# Battery_Reader.net
KiCad netlist of a schematic drawn in Altium Designer
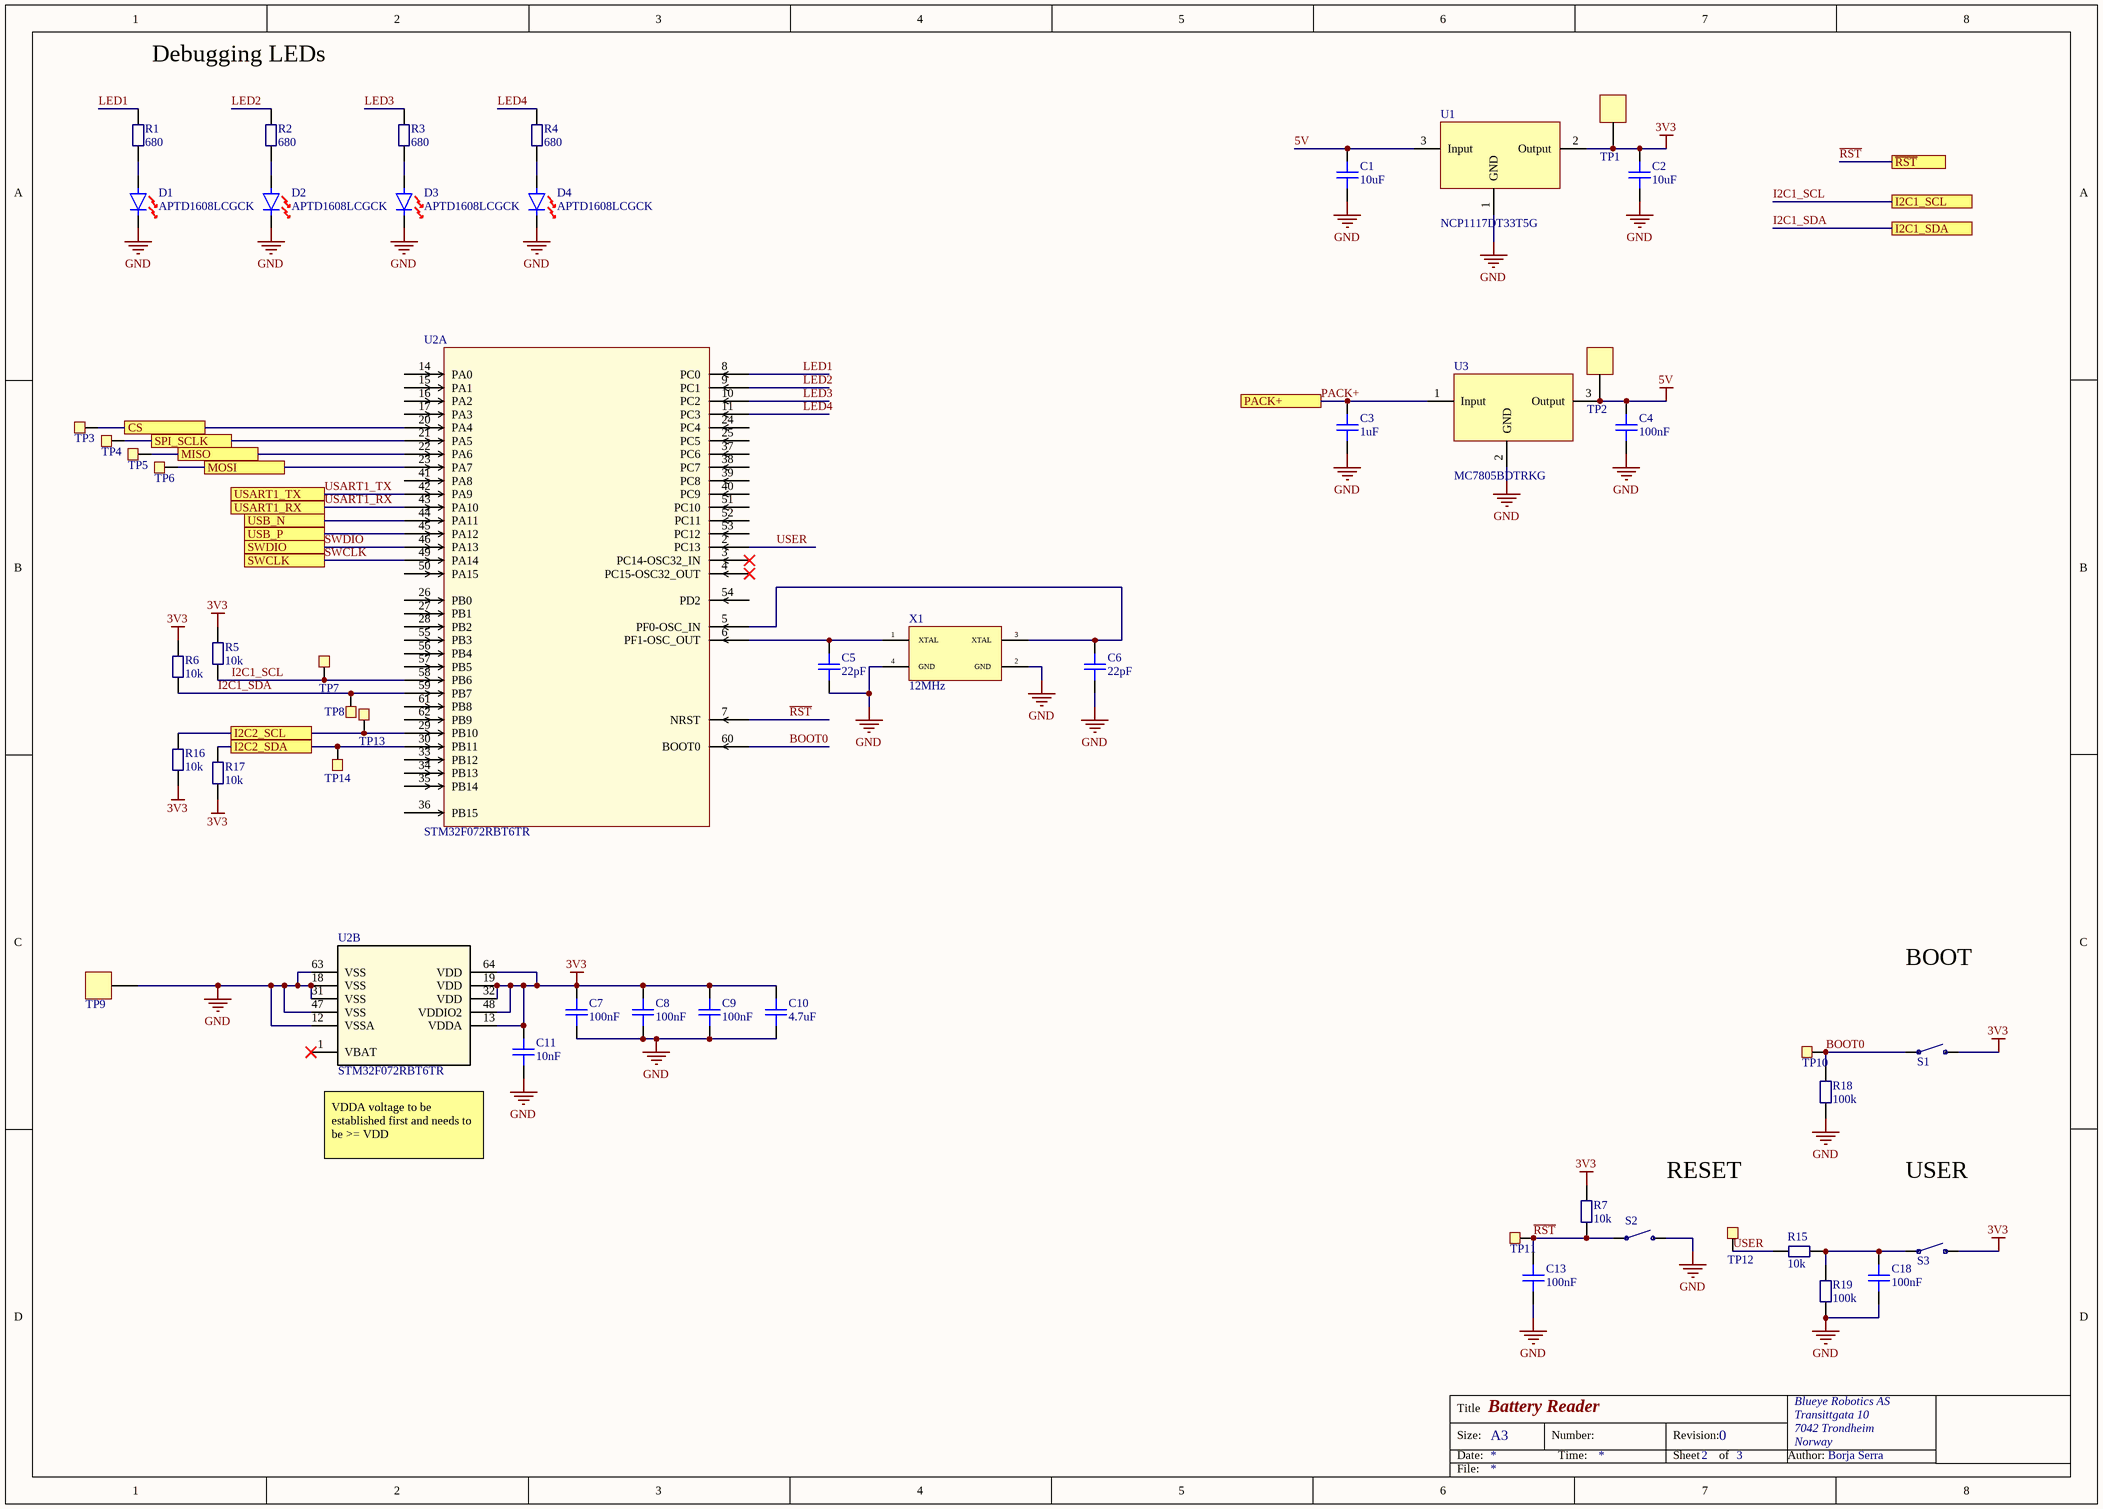
[diagram p0: Battery Reader.SchDoc]

(export (version "E")
  (design (tool "Eeschema 10.0.6"))
  (components
    (comp (ref "C1")
      (value "10uF")
      (footprint "1206 CAPACITOR")
      (description "CAP CER 10UF 35V X7R 1206")
      (fields (field (name "MPN") "GMK316AB7106KL-TR") (field (name "MANUFACTURER") "Taiyo Yuden"))
      (libsource (lib "Battery Reader") (part "CAP CER 10UF 35V X7R 1206"))
    )
    (comp (ref "C2")
      (value "10uF")
      (footprint "1206 CAPACITOR")
      (description "CAP CER 10UF 35V X7R 1206")
      (fields (field (name "MPN") "GMK316AB7106KL-TR") (field (name "MANUFACTURER") "Taiyo Yuden"))
      (libsource (lib "Battery Reader") (part "CAP CER 10UF 35V X7R 1206"))
    )
    (comp (ref "C3")
      (value "1uF")
      (footprint "1206 CAPACITOR")
      (description "Multilayer Ceramic Capacitors MLCC - SMD/SMT 1206 1.0uF 50V X7R 20%")
      (fields (field (name "MANUFACTURER") "TDK") (field (name "MPN") "C3216X7R1H105M160AB"))
      (libsource (lib "Battery Reader") (part "Capacitor 1uF 50V"))
    )
    (comp (ref "C4")
      (value "100nF")
      (footprint "0603 Capacitor")
      (description "CAP CER 0.1UF 50V X7R 0603")
      (fields
        (field (name "MPN") "CL10B104KB8NNNC")
        (field (name "MANUFACTURER") "Samsung Electro-Mechanics")
      )
      (libsource (lib "Battery Reader") (part "CAP CER 0.1UF 50V X7R 0603"))
    )
    (comp (ref "C5")
      (value "22pF")
      (footprint "0603 Capacitor")
      (description "CAP CER 22PF 50V X7R 0603")
      (fields (field (name "MPN") "06035C220JAT2A") (field (name "MANUFACTURER") "AVX Corporation"))
      (libsource (lib "Battery Reader") (part "CAP CER 22PF 50V X7R 0603"))
    )
    (comp (ref "C6")
      (value "22pF")
      (footprint "0603 Capacitor")
      (description "CAP CER 22PF 50V X7R 0603")
      (fields (field (name "MPN") "06035C220JAT2A") (field (name "MANUFACTURER") "AVX Corporation"))
      (libsource (lib "Battery Reader") (part "CAP CER 22PF 50V X7R 0603"))
    )
    (comp (ref "C7")
      (value "100nF")
      (footprint "0603 Capacitor")
      (description "CAP CER 0.1UF 50V X7R 0603")
      (fields
        (field (name "MPN") "CL10B104KB8NNNC")
        (field (name "MANUFACTURER") "Samsung Electro-Mechanics")
      )
      (libsource (lib "Battery Reader") (part "CAP CER 0.1UF 50V X7R 0603"))
    )
    (comp (ref "C8")
      (value "100nF")
      (footprint "0603 Capacitor")
      (description "CAP CER 0.1UF 50V X7R 0603")
      (fields
        (field (name "MPN") "CL10B104KB8NNNC")
        (field (name "MANUFACTURER") "Samsung Electro-Mechanics")
      )
      (libsource (lib "Battery Reader") (part "CAP CER 0.1UF 50V X7R 0603"))
    )
    (comp (ref "C9")
      (value "100nF")
      (footprint "0603 Capacitor")
      (description "CAP CER 0.1UF 50V X7R 0603")
      (fields
        (field (name "MPN") "CL10B104KB8NNNC")
        (field (name "MANUFACTURER") "Samsung Electro-Mechanics")
      )
      (libsource (lib "Battery Reader") (part "CAP CER 0.1UF 50V X7R 0603"))
    )
    (comp (ref "C10")
      (value "4.7uF")
      (footprint "0805 Capacitor")
      (description "Multilayer Ceramic Capacitors MLCC - SMD/SMT 4.7uF 25Volts 10%")
      (fields (field (name "MANUFACTURER") "Murata Electronics") (field (name "MPN") "GRM21BR61E475KA12K"))
      (libsource (lib "Battery Reader") (part "Capacitor 4.7uF 25V"))
    )
    (comp (ref "C11")
      (value "10nF")
      (footprint "0603 Capacitor")
      (description "Multilayer CeramicCapacitors MLCC - SMD/SMT 100volts .01uF 10% X7R AUTO ESD")
      (fields (field (name "MPN") "C0603C103K1RECAUTO") (field (name "MANUFACTURER") "Kemet"))
      (libsource (lib "Battery Reader") (part "Capacitor 10nF"))
    )
    (comp (ref "C13")
      (value "100nF")
      (footprint "0603 Capacitor")
      (description "CAP CER 0.1UF 50V X7R 0603")
      (fields
        (field (name "MPN") "CL10B104KB8NNNC")
        (field (name "MANUFACTURER") "Samsung Electro-Mechanics")
      )
      (libsource (lib "Battery Reader") (part "CAP CER 0.1UF 50V X7R 0603"))
    )
    (comp (ref "C18")
      (value "100nF")
      (footprint "0603 Capacitor")
      (description "CAP CER 0.1UF 50V X7R 0603")
      (fields
        (field (name "MPN") "CL10B104KB8NNNC")
        (field (name "MANUFACTURER") "Samsung Electro-Mechanics")
      )
      (libsource (lib "Battery Reader") (part "CAP CER 0.1UF 50V X7R 0603"))
    )
    (comp (ref "D1")
      (value "APTD1608LCGCK")
      (footprint "0603 LED")
      (description "Standard LEDs - SMD 0603 Dome Lens LED Green- 570nm")
      (fields (field (name "MANUFACTURER") "Kingbright"))
      (libsource (lib "Battery Reader") (part "Standard LEDs - SMD 0603 Dome Lens LED Green- 570nm"))
    )
    (comp (ref "D2")
      (value "APTD1608LCGCK")
      (footprint "0603 LED")
      (description "Standard LEDs - SMD 0603 Dome Lens LED Green- 570nm")
      (fields (field (name "MANUFACTURER") "Kingbright"))
      (libsource (lib "Battery Reader") (part "Standard LEDs - SMD 0603 Dome Lens LED Green- 570nm"))
    )
    (comp (ref "D3")
      (value "APTD1608LCGCK")
      (footprint "0603 LED")
      (description "Standard LEDs - SMD 0603 Dome Lens LED Green- 570nm")
      (fields (field (name "MANUFACTURER") "Kingbright"))
      (libsource (lib "Battery Reader") (part "Standard LEDs - SMD 0603 Dome Lens LED Green- 570nm"))
    )
    (comp (ref "D4")
      (value "APTD1608LCGCK")
      (footprint "0603 LED")
      (description "Standard LEDs - SMD 0603 Dome Lens LED Green- 570nm")
      (fields (field (name "MANUFACTURER") "Kingbright"))
      (libsource (lib "Battery Reader") (part "Standard LEDs - SMD 0603 Dome Lens LED Green- 570nm"))
    )
    (comp (ref "R1")
      (value "680")
      (footprint "0603 Resistor")
      (description "Thick Film Resistors - SMD 0603 680ohms 5% AEC-Q200")
      (fields (field (name "MPN") "ERJ-3GEYJ681V") (field (name "MANUFACTURER") "Panasonic"))
      (libsource (lib "Battery Reader") (part "resistor 680 ohm"))
    )
    (comp (ref "R2")
      (value "680")
      (footprint "0603 Resistor")
      (description "Thick Film Resistors - SMD 0603 680ohms 5% AEC-Q200")
      (fields (field (name "MPN") "ERJ-3GEYJ681V") (field (name "MANUFACTURER") "Panasonic"))
      (libsource (lib "Battery Reader") (part "resistor 680 ohm"))
    )
    (comp (ref "R3")
      (value "680")
      (footprint "0603 Resistor")
      (description "Thick Film Resistors - SMD 0603 680ohms 5% AEC-Q200")
      (fields (field (name "MPN") "ERJ-3GEYJ681V") (field (name "MANUFACTURER") "Panasonic"))
      (libsource (lib "Battery Reader") (part "resistor 680 ohm"))
    )
    (comp (ref "R4")
      (value "680")
      (footprint "0603 Resistor")
      (description "Thick Film Resistors - SMD 0603 680ohms 5% AEC-Q200")
      (fields (field (name "MPN") "ERJ-3GEYJ681V") (field (name "MANUFACTURER") "Panasonic"))
      (libsource (lib "Battery Reader") (part "resistor 680 ohm"))
    )
    (comp (ref "R5")
      (value "10k")
      (footprint "0603 Resistor")
      (description "RES SMD 10K OHM 5% 1/10W 0603")
      (fields (field (name "MANUFACTURER") "Yageo") (field (name "MPN") "RC0603JR-0710KL"))
      (libsource (lib "Battery Reader") (part "RES SMD 10K OHM 5% 1/10W 0603"))
    )
    (comp (ref "R6")
      (value "10k")
      (footprint "0603 Resistor")
      (description "RES SMD 10K OHM 5% 1/10W 0603")
      (fields (field (name "MANUFACTURER") "Yageo") (field (name "MPN") "RC0603JR-0710KL"))
      (libsource (lib "Battery Reader") (part "RES SMD 10K OHM 5% 1/10W 0603"))
    )
    (comp (ref "R7")
      (value "10k")
      (footprint "0603 Resistor")
      (description "RES SMD 10K OHM 5% 1/10W 0603")
      (fields (field (name "MANUFACTURER") "Yageo") (field (name "MPN") "RC0603JR-0710KL"))
      (libsource (lib "Battery Reader") (part "RES SMD 10K OHM 5% 1/10W 0603"))
    )
    (comp (ref "R15")
      (value "10k")
      (footprint "0603 Resistor")
      (description "RES SMD 10K OHM 5% 1/10W 0603")
      (fields (field (name "MANUFACTURER") "Yageo") (field (name "MPN") "RC0603JR-0710KL"))
      (libsource (lib "Battery Reader") (part "RES SMD 10K OHM 5% 1/10W 0603"))
    )
    (comp (ref "R16")
      (value "10k")
      (footprint "0603 Resistor")
      (description "RES SMD 10K OHM 5% 1/10W 0603")
      (fields (field (name "MANUFACTURER") "Yageo") (field (name "MPN") "RC0603JR-0710KL"))
      (libsource (lib "Battery Reader") (part "RES SMD 10K OHM 5% 1/10W 0603"))
    )
    (comp (ref "R17")
      (value "10k")
      (footprint "0603 Resistor")
      (description "RES SMD 10K OHM 5% 1/10W 0603")
      (fields (field (name "MANUFACTURER") "Yageo") (field (name "MPN") "RC0603JR-0710KL"))
      (libsource (lib "Battery Reader") (part "RES SMD 10K OHM 5% 1/10W 0603"))
    )
    (comp (ref "R18")
      (value "100k")
      (footprint "0603 Resistor")
      (description "RES SMD 100K OHM 5% 1/10W 0603")
      (fields (field (name "MPN") "RC0603JR-07100KL") (field (name "MANUFACTURER") "Yageo"))
      (libsource (lib "Battery Reader") (part "RES SMD 100K OHM 5% 1/10W 0603"))
    )
    (comp (ref "R19")
      (value "100k")
      (footprint "0603 Resistor")
      (description "RES SMD 100K OHM 5% 1/10W 0603")
      (fields (field (name "MPN") "RC0603JR-07100KL") (field (name "MANUFACTURER") "Yageo"))
      (libsource (lib "Battery Reader") (part "RES SMD 100K OHM 5% 1/10W 0603"))
    )
    (comp (ref "S1")
      (value "Tactile Switches Reset")
      (footprint "Tact Switch - panasonic")
      (description "Tactile Switches 6.0x3.5mm SMD Light Touch Switch")
      (fields (field (name "MANUFACTURER") "Panasonic") (field (name "MPN") "EVQ-PE105K"))
      (libsource (lib "Battery Reader") (part "Tactile Switches Reset"))
    )
    (comp (ref "S2")
      (value "Tactile Switches Reset")
      (footprint "Tact Switch - panasonic")
      (description "Tactile Switches 6.0x3.5mm SMD Light Touch Switch")
      (fields (field (name "MANUFACTURER") "Panasonic") (field (name "MPN") "EVQ-PE105K"))
      (libsource (lib "Battery Reader") (part "Tactile Switches Reset"))
    )
    (comp (ref "S3")
      (value "Tactile Switches Reset")
      (footprint "Tact Switch - panasonic")
      (description "Tactile Switches 6.0x3.5mm SMD Light Touch Switch")
      (fields (field (name "MANUFACTURER") "Panasonic") (field (name "MPN") "EVQ-PE105K"))
      (libsource (lib "Battery Reader") (part "Tactile Switches Reset"))
    )
    (comp (ref "TP1")
      (value "3122-2-00-15-00-00-08-0")
      (footprint "3122-2-00-15-00-00-08-0")
      (description "CONN PC PIN CIRC 0.040DIA GOLD")
      (fields
        (field (name "MANUFACTURER") "Mill-Max")
        (field (name "MANUFACTURER PART NUMBER") "3123-2-00-15-00-00-08-0")
      )
      (libsource (lib "Battery Reader") (part "3122-2-00-15-00-00-08-0"))
    )
    (comp (ref "TP2")
      (value "3122-2-00-15-00-00-08-0")
      (footprint "3122-2-00-15-00-00-08-0")
      (description "CONN PC PIN CIRC 0.040DIA GOLD")
      (fields
        (field (name "MANUFACTURER") "Mill-Max")
        (field (name "MANUFACTURER PART NUMBER") "3123-2-00-15-00-00-08-0")
      )
      (libsource (lib "Battery Reader") (part "3122-2-00-15-00-00-08-0"))
    )
    (comp (ref "TP3")
      (value "Testpoint")
      (footprint "Testpoint")
      (libsource (lib "Battery Reader") (part "Testpoint"))
    )
    (comp (ref "TP4")
      (value "Testpoint")
      (footprint "Testpoint")
      (libsource (lib "Battery Reader") (part "Testpoint"))
    )
    (comp (ref "TP5")
      (value "Testpoint")
      (footprint "Testpoint")
      (libsource (lib "Battery Reader") (part "Testpoint"))
    )
    (comp (ref "TP6")
      (value "Testpoint")
      (footprint "Testpoint")
      (libsource (lib "Battery Reader") (part "Testpoint"))
    )
    (comp (ref "TP7") (value "Testpoint") (footprint "Testpoint") (libsource (lib "") (part "Testpoint_1")))
    (comp (ref "TP8") (value "Testpoint") (footprint "Testpoint") (libsource (lib "") (part "Testpoint_2")))
    (comp (ref "TP9")
      (value "3122-2-00-15-00-00-08-0")
      (footprint "3122-2-00-15-00-00-08-0")
      (description "CONN PC PIN CIRC 0.040DIA GOLD")
      (fields
        (field (name "MANUFACTURER") "Mill-Max")
        (field (name "MANUFACTURER PART NUMBER") "3123-2-00-15-00-00-08-0")
      )
      (libsource (lib "") (part "3122-2-00-15-00-00-08-0_1"))
    )
    (comp (ref "TP10")
      (value "Testpoint")
      (footprint "Testpoint")
      (libsource (lib "Battery Reader") (part "Testpoint"))
    )
    (comp (ref "TP11")
      (value "Testpoint")
      (footprint "Testpoint")
      (libsource (lib "Battery Reader") (part "Testpoint"))
    )
    (comp (ref "TP12") (value "Testpoint") (footprint "Testpoint") (libsource (lib "") (part "Testpoint_1")))
    (comp (ref "TP13") (value "Testpoint") (footprint "Testpoint") (libsource (lib "") (part "Testpoint_1")))
    (comp (ref "TP14") (value "Testpoint") (footprint "Testpoint") (libsource (lib "") (part "Testpoint_2")))
    (comp (ref "U1")
      (value "NCP1117DT33T5G")
      (footprint "DPAK-3")
      (description "IC REG LINEAR 3.3V 1A DPAK-3")
      (fields (field (name "MANUFACTURER") "ON Semiconductor"))
      (libsource (lib "Battery Reader") (part "IC REG LINEAR 3.3V 1A DPAK-3"))
    )
    (comp (ref "U2")
      (value "STM32F072RBT6TR")
      (footprint "LQFP64-10x10mm")
      (fields (field (name "COPYRIGHT") "Copyright (C) 2016 Accelerated Designs. All rights reserved"))
      (libsource (lib "Battery Reader") (part "STM32F072RBT6TR"))
    )
    (comp (ref "U3")
      (value "MC7805BDTRKG")
      (footprint "DPAK-3")
      (description "IC REG LINEAR 5V 1A DPAK-3")
      (fields (field (name "MANUFACTURER") "ON Semiconductor"))
      (libsource (lib "Battery Reader") (part "IC REG LINEAR 5V 1A DPAK-3"))
    )
    (comp (ref "X1")
      (value "12MHz")
      (footprint "FH1200001 12MHz")
      (description "Crystal 12MHz")
      (fields (field (name "MANUFACTURER") "Pericom") (field (name "MPN") "FH1200001"))
      (libsource (lib "Battery Reader") (part "Crystal 12MHz"))
    )
  )
  (nets
    (net (code "1") (name "/BOOT0") (class "Default")
      (node (ref "R18") (pin "2") (pinfunction "2_2") (pintype "passive"))
      (node (ref "S1") (pin "1") (pinfunction "1_1") (pintype "passive"))
      (node (ref "TP10") (pin "1") (pinfunction "1_1") (pintype "passive"))
      (node (ref "U2") (pin "60") (pinfunction "BOOT0_60") (pintype "passive"))
    )
    (net (code "2") (name "/CS") (class "Default")
      (node (ref "TP3") (pin "1") (pinfunction "1_1") (pintype "passive"))
      (node (ref "U2") (pin "20") (pinfunction "PA4_20") (pintype "passive"))
    )
    (net (code "3") (name "/I2C1_SCL") (class "Default")
      (node (ref "R5") (pin "1") (pinfunction "1_1") (pintype "passive"))
      (node (ref "TP7") (pin "1") (pinfunction "1_1") (pintype "passive"))
      (node (ref "U2") (pin "58") (pinfunction "PB6_58") (pintype "passive"))
    )
    (net (code "4") (name "/I2C1_SDA") (class "Default")
      (node (ref "R6") (pin "1") (pinfunction "1_1") (pintype "passive"))
      (node (ref "TP8") (pin "1") (pinfunction "1_1") (pintype "passive"))
      (node (ref "U2") (pin "59") (pinfunction "PB7_59") (pintype "passive"))
    )
    (net (code "5") (name "/I2C2_SCL") (class "Default")
      (node (ref "R16") (pin "2") (pinfunction "2_2") (pintype "passive"))
      (node (ref "TP13") (pin "1") (pinfunction "1_1") (pintype "passive"))
      (node (ref "U2") (pin "29") (pinfunction "PB10_29") (pintype "passive"))
    )
    (net (code "6") (name "/I2C2_SDA") (class "Default")
      (node (ref "R17") (pin "2") (pinfunction "2_2") (pintype "passive"))
      (node (ref "TP14") (pin "1") (pinfunction "1_1") (pintype "passive"))
      (node (ref "U2") (pin "30") (pinfunction "PB11_30") (pintype "passive"))
    )
    (net (code "7") (name "/LED1") (class "Default")
      (node (ref "R1") (pin "2") (pinfunction "2_2") (pintype "passive"))
      (node (ref "U2") (pin "8") (pinfunction "PC0_8") (pintype "passive"))
    )
    (net (code "8") (name "/LED2") (class "Default")
      (node (ref "R2") (pin "2") (pinfunction "2_2") (pintype "passive"))
      (node (ref "U2") (pin "9") (pinfunction "PC1_9") (pintype "passive"))
    )
    (net (code "9") (name "/LED3") (class "Default")
      (node (ref "R3") (pin "2") (pinfunction "2_2") (pintype "passive"))
      (node (ref "U2") (pin "10") (pinfunction "PC2_10") (pintype "passive"))
    )
    (net (code "10") (name "/LED4") (class "Default")
      (node (ref "R4") (pin "2") (pinfunction "2_2") (pintype "passive"))
      (node (ref "U2") (pin "11") (pinfunction "PC3_11") (pintype "passive"))
    )
    (net (code "11") (name "/MISO") (class "Default")
      (node (ref "TP5") (pin "1") (pinfunction "1_1") (pintype "passive"))
      (node (ref "U2") (pin "22") (pinfunction "PA6_22") (pintype "passive"))
    )
    (net (code "12") (name "/MOSI") (class "Default")
      (node (ref "TP6") (pin "1") (pinfunction "1_1") (pintype "passive"))
      (node (ref "U2") (pin "23") (pinfunction "PA7_23") (pintype "passive"))
    )
    (net (code "13") (name "/PACK+") (class "Default")
      (node (ref "C3") (pin "2") (pinfunction "2_2") (pintype "passive"))
      (node (ref "U3") (pin "1") (pinfunction "Input_1") (pintype "passive"))
    )
    (net (code "14") (name "/SPI_SCLK") (class "Default")
      (node (ref "TP4") (pin "1") (pinfunction "1_1") (pintype "passive"))
      (node (ref "U2") (pin "21") (pinfunction "PA5_21") (pintype "passive"))
    )
    (net (code "15") (name "/SWCLK") (class "Default")
      (node (ref "U2") (pin "49") (pinfunction "PA14_49") (pintype "passive"))
    )
    (net (code "16") (name "/SWDIO") (class "Default")
      (node (ref "U2") (pin "46") (pinfunction "PA13_46") (pintype "passive"))
    )
    (net (code "17") (name "/USART1_RX") (class "Default")
      (node (ref "U2") (pin "43") (pinfunction "PA10_43") (pintype "passive"))
    )
    (net (code "18") (name "/USART1_TX") (class "Default")
      (node (ref "U2") (pin "42") (pinfunction "PA9_42") (pintype "passive"))
    )
    (net (code "19") (name "/USB_N") (class "Default")
      (node (ref "U2") (pin "44") (pinfunction "PA11_44") (pintype "passive"))
    )
    (net (code "20") (name "/USB_P") (class "Default")
      (node (ref "U2") (pin "45") (pinfunction "PA12_45") (pintype "passive"))
    )
    (net (code "21") (name "/USER") (class "Default")
      (node (ref "R15") (pin "1") (pinfunction "1_1") (pintype "passive"))
      (node (ref "TP12") (pin "1") (pinfunction "1_1") (pintype "passive"))
      (node (ref "U2") (pin "2") (pinfunction "PC13_2") (pintype "passive"))
    )
    (net (code "22") (name "/~{RST}") (class "Default")
      (node (ref "C13") (pin "2") (pinfunction "2_2") (pintype "passive"))
      (node (ref "R7") (pin "1") (pinfunction "1_1") (pintype "passive"))
      (node (ref "S2") (pin "1") (pinfunction "1_1") (pintype "passive"))
      (node (ref "TP11") (pin "1") (pinfunction "1_1") (pintype "passive"))
      (node (ref "U2") (pin "7") (pinfunction "NRST_7") (pintype "passive"))
    )
    (net (code "23") (name "3V3") (class "Default")
      (node (ref "C10") (pin "2") (pinfunction "2_2") (pintype "passive"))
      (node (ref "C11") (pin "2") (pinfunction "2_2") (pintype "passive"))
      (node (ref "C2") (pin "2") (pinfunction "2_2") (pintype "passive"))
      (node (ref "C7") (pin "2") (pinfunction "2_2") (pintype "passive"))
      (node (ref "C8") (pin "2") (pinfunction "2_2") (pintype "passive"))
      (node (ref "C9") (pin "2") (pinfunction "2_2") (pintype "passive"))
      (node (ref "R16") (pin "1") (pinfunction "1_1") (pintype "passive"))
      (node (ref "R17") (pin "1") (pinfunction "1_1") (pintype "passive"))
      (node (ref "R5") (pin "2") (pinfunction "2_2") (pintype "passive"))
      (node (ref "R6") (pin "2") (pinfunction "2_2") (pintype "passive"))
      (node (ref "R7") (pin "2") (pinfunction "2_2") (pintype "passive"))
      (node (ref "S1") (pin "2") (pinfunction "2_2") (pintype "passive"))
      (node (ref "S3") (pin "2") (pinfunction "2_2") (pintype "passive"))
      (node (ref "TP1") (pin "1") (pintype "passive"))
      (node (ref "U1") (pin "2") (pinfunction "Output_2") (pintype "passive"))
      (node (ref "U2") (pin "13") (pinfunction "VDDA_13") (pintype "power_in"))
      (node (ref "U2") (pin "19") (pinfunction "VDD_19") (pintype "power_in"))
      (node (ref "U2") (pin "32") (pinfunction "VDD_32") (pintype "power_in"))
      (node (ref "U2") (pin "48") (pinfunction "VDDIO2_48") (pintype "passive"))
      (node (ref "U2") (pin "64") (pinfunction "VDD_64") (pintype "passive"))
    )
    (net (code "24") (name "5V") (class "Default")
      (node (ref "C1") (pin "2") (pinfunction "2_2") (pintype "passive"))
      (node (ref "C4") (pin "2") (pinfunction "2_2") (pintype "passive"))
      (node (ref "TP2") (pin "1") (pintype "passive"))
      (node (ref "U1") (pin "3") (pinfunction "Input_3") (pintype "passive"))
      (node (ref "U3") (pin "3") (pinfunction "Output_3") (pintype "passive"))
    )
    (net (code "25") (name "GND") (class "Default")
      (node (ref "C1") (pin "1") (pinfunction "1_1") (pintype "passive"))
      (node (ref "C10") (pin "1") (pinfunction "1_1") (pintype "passive"))
      (node (ref "C11") (pin "1") (pinfunction "1_1") (pintype "passive"))
      (node (ref "C13") (pin "1") (pinfunction "1_1") (pintype "passive"))
      (node (ref "C18") (pin "1") (pinfunction "1_1") (pintype "passive"))
      (node (ref "C2") (pin "1") (pinfunction "1_1") (pintype "passive"))
      (node (ref "C3") (pin "1") (pinfunction "1_1") (pintype "passive"))
      (node (ref "C4") (pin "1") (pinfunction "1_1") (pintype "passive"))
      (node (ref "C5") (pin "1") (pinfunction "1_1") (pintype "passive"))
      (node (ref "C6") (pin "1") (pinfunction "1_1") (pintype "passive"))
      (node (ref "C7") (pin "1") (pinfunction "1_1") (pintype "passive"))
      (node (ref "C8") (pin "1") (pinfunction "1_1") (pintype "passive"))
      (node (ref "C9") (pin "1") (pinfunction "1_1") (pintype "passive"))
      (node (ref "D1") (pin "1") (pintype "passive"))
      (node (ref "D2") (pin "1") (pintype "passive"))
      (node (ref "D3") (pin "1") (pintype "passive"))
      (node (ref "D4") (pin "1") (pintype "passive"))
      (node (ref "R18") (pin "1") (pinfunction "1_1") (pintype "passive"))
      (node (ref "R19") (pin "1") (pinfunction "1_1") (pintype "passive"))
      (node (ref "S2") (pin "2") (pinfunction "2_2") (pintype "passive"))
      (node (ref "TP9") (pin "1") (pintype "passive"))
      (node (ref "U1") (pin "1") (pinfunction "GND_1") (pintype "passive"))
      (node (ref "U2") (pin "12") (pinfunction "VSSA_12") (pintype "power_in"))
      (node (ref "U2") (pin "18") (pinfunction "VSS_18") (pintype "power_in"))
      (node (ref "U2") (pin "31") (pinfunction "VSS_31") (pintype "power_in"))
      (node (ref "U2") (pin "47") (pinfunction "VSS_47") (pintype "passive"))
      (node (ref "U2") (pin "63") (pinfunction "VSS_63") (pintype "passive"))
      (node (ref "U3") (pin "2") (pinfunction "GND_2") (pintype "passive"))
      (node (ref "X1") (pin "2") (pinfunction "GND_2") (pintype "passive"))
      (node (ref "X1") (pin "4") (pinfunction "GND_4") (pintype "passive"))
    )
    (net (code "26") (name "Net-(C18-Pad2)") (class "Default")
      (node (ref "C18") (pin "2") (pinfunction "2_2") (pintype "passive"))
      (node (ref "R15") (pin "2") (pinfunction "2_2") (pintype "passive"))
      (node (ref "R19") (pin "2") (pinfunction "2_2") (pintype "passive"))
      (node (ref "S3") (pin "1") (pinfunction "1_1") (pintype "passive"))
    )
    (net (code "27") (name "Net-(D1-Pad2)") (class "Default")
      (node (ref "D1") (pin "2") (pintype "passive"))
      (node (ref "R1") (pin "1") (pinfunction "1_1") (pintype "passive"))
    )
    (net (code "28") (name "Net-(D2-Pad2)") (class "Default")
      (node (ref "D2") (pin "2") (pintype "passive"))
      (node (ref "R2") (pin "1") (pinfunction "1_1") (pintype "passive"))
    )
    (net (code "29") (name "Net-(D3-Pad2)") (class "Default")
      (node (ref "D3") (pin "2") (pintype "passive"))
      (node (ref "R3") (pin "1") (pinfunction "1_1") (pintype "passive"))
    )
    (net (code "30") (name "Net-(D4-Pad2)") (class "Default")
      (node (ref "D4") (pin "2") (pintype "passive"))
      (node (ref "R4") (pin "1") (pinfunction "1_1") (pintype "passive"))
    )
    (net (code "31") (name "Net-(U2A-PF0-OSC_IN)") (class "Default")
      (node (ref "C6") (pin "2") (pinfunction "2_2") (pintype "passive"))
      (node (ref "U2") (pin "5") (pinfunction "PF0-OSC_IN_5") (pintype "passive"))
      (node (ref "X1") (pin "3") (pinfunction "XTAL_3") (pintype "passive"))
    )
    (net (code "32") (name "Net-(U2A-PF1-OSC_OUT)") (class "Default")
      (node (ref "C5") (pin "2") (pinfunction "2_2") (pintype "passive"))
      (node (ref "U2") (pin "6") (pinfunction "PF1-OSC_OUT_6") (pintype "passive"))
      (node (ref "X1") (pin "1") (pinfunction "XTAL_1") (pintype "passive"))
    )
    (net (code "33") (name "unconnected-(U2A-PA0-Pad14)") (class "Default")
      (node (ref "U2") (pin "14") (pinfunction "PA0_14") (pintype "passive"))
    )
    (net (code "34") (name "unconnected-(U2A-PA1-Pad15)") (class "Default")
      (node (ref "U2") (pin "15") (pinfunction "PA1_15") (pintype "passive"))
    )
    (net (code "35") (name "unconnected-(U2A-PA2-Pad16)") (class "Default")
      (node (ref "U2") (pin "16") (pinfunction "PA2_16") (pintype "passive"))
    )
    (net (code "36") (name "unconnected-(U2A-PA3-Pad17)") (class "Default")
      (node (ref "U2") (pin "17") (pinfunction "PA3_17") (pintype "passive"))
    )
    (net (code "37") (name "unconnected-(U2A-PA8-Pad41)") (class "Default")
      (node (ref "U2") (pin "41") (pinfunction "PA8_41") (pintype "passive"))
    )
    (net (code "38") (name "unconnected-(U2A-PA15-Pad50)") (class "Default")
      (node (ref "U2") (pin "50") (pinfunction "PA15_50") (pintype "passive"))
    )
    (net (code "39") (name "unconnected-(U2A-PB0-Pad26)") (class "Default")
      (node (ref "U2") (pin "26") (pinfunction "PB0_26") (pintype "passive"))
    )
    (net (code "40") (name "unconnected-(U2A-PB1-Pad27)") (class "Default")
      (node (ref "U2") (pin "27") (pinfunction "PB1_27") (pintype "passive"))
    )
    (net (code "41") (name "unconnected-(U2A-PB2-Pad28)") (class "Default")
      (node (ref "U2") (pin "28") (pinfunction "PB2_28") (pintype "passive"))
    )
    (net (code "42") (name "unconnected-(U2A-PB3-Pad55)") (class "Default")
      (node (ref "U2") (pin "55") (pinfunction "PB3_55") (pintype "passive"))
    )
    (net (code "43") (name "unconnected-(U2A-PB4-Pad56)") (class "Default")
      (node (ref "U2") (pin "56") (pinfunction "PB4_56") (pintype "passive"))
    )
    (net (code "44") (name "unconnected-(U2A-PB5-Pad57)") (class "Default")
      (node (ref "U2") (pin "57") (pinfunction "PB5_57") (pintype "passive"))
    )
    (net (code "45") (name "unconnected-(U2A-PB8-Pad61)") (class "Default")
      (node (ref "U2") (pin "61") (pinfunction "PB8_61") (pintype "passive"))
    )
    (net (code "46") (name "unconnected-(U2A-PB9-Pad62)") (class "Default")
      (node (ref "U2") (pin "62") (pinfunction "PB9_62") (pintype "passive"))
    )
    (net (code "47") (name "unconnected-(U2A-PB12-Pad33)") (class "Default")
      (node (ref "U2") (pin "33") (pinfunction "PB12_33") (pintype "passive"))
    )
    (net (code "48") (name "unconnected-(U2A-PB13-Pad34)") (class "Default")
      (node (ref "U2") (pin "34") (pinfunction "PB13_34") (pintype "passive"))
    )
    (net (code "49") (name "unconnected-(U2A-PB14-Pad35)") (class "Default")
      (node (ref "U2") (pin "35") (pinfunction "PB14_35") (pintype "passive"))
    )
    (net (code "50") (name "unconnected-(U2A-PB15-Pad36)") (class "Default")
      (node (ref "U2") (pin "36") (pinfunction "PB15_36") (pintype "passive"))
    )
    (net (code "51") (name "unconnected-(U2A-PC4-Pad24)") (class "Default")
      (node (ref "U2") (pin "24") (pinfunction "PC4_24") (pintype "passive"))
    )
    (net (code "52") (name "unconnected-(U2A-PC5-Pad25)") (class "Default")
      (node (ref "U2") (pin "25") (pinfunction "PC5_25") (pintype "passive"))
    )
    (net (code "53") (name "unconnected-(U2A-PC6-Pad37)") (class "Default")
      (node (ref "U2") (pin "37") (pinfunction "PC6_37") (pintype "passive"))
    )
    (net (code "54") (name "unconnected-(U2A-PC7-Pad38)") (class "Default")
      (node (ref "U2") (pin "38") (pinfunction "PC7_38") (pintype "passive"))
    )
    (net (code "55") (name "unconnected-(U2A-PC8-Pad39)") (class "Default")
      (node (ref "U2") (pin "39") (pinfunction "PC8_39") (pintype "passive"))
    )
    (net (code "56") (name "unconnected-(U2A-PC9-Pad40)") (class "Default")
      (node (ref "U2") (pin "40") (pinfunction "PC9_40") (pintype "passive"))
    )
    (net (code "57") (name "unconnected-(U2A-PC10-Pad51)") (class "Default")
      (node (ref "U2") (pin "51") (pinfunction "PC10_51") (pintype "passive"))
    )
    (net (code "58") (name "unconnected-(U2A-PC11-Pad52)") (class "Default")
      (node (ref "U2") (pin "52") (pinfunction "PC11_52") (pintype "passive"))
    )
    (net (code "59") (name "unconnected-(U2A-PC12-Pad53)") (class "Default")
      (node (ref "U2") (pin "53") (pinfunction "PC12_53") (pintype "passive"))
    )
    (net (code "60") (name "unconnected-(U2A-PC14-OSC32_IN-Pad3)") (class "Default")
      (node (ref "U2") (pin "3") (pinfunction "PC14-OSC32_IN_3") (pintype "passive+no_connect"))
    )
    (net (code "61") (name "unconnected-(U2A-PC15-OSC32_OUT-Pad4)") (class "Default")
      (node (ref "U2") (pin "4") (pinfunction "PC15-OSC32_OUT_4") (pintype "passive+no_connect"))
    )
    (net (code "62") (name "unconnected-(U2A-PD2-Pad54)") (class "Default")
      (node (ref "U2") (pin "54") (pinfunction "PD2_54") (pintype "passive"))
    )
    (net (code "63") (name "unconnected-(U2B-VBAT-Pad1)") (class "Default")
      (node (ref "U2") (pin "1") (pinfunction "VBAT_1") (pintype "power_in+no_connect"))
    )
  )
)
